# 9V_Converter.net
KiCad netlist of a schematic drawn in Altium Designer
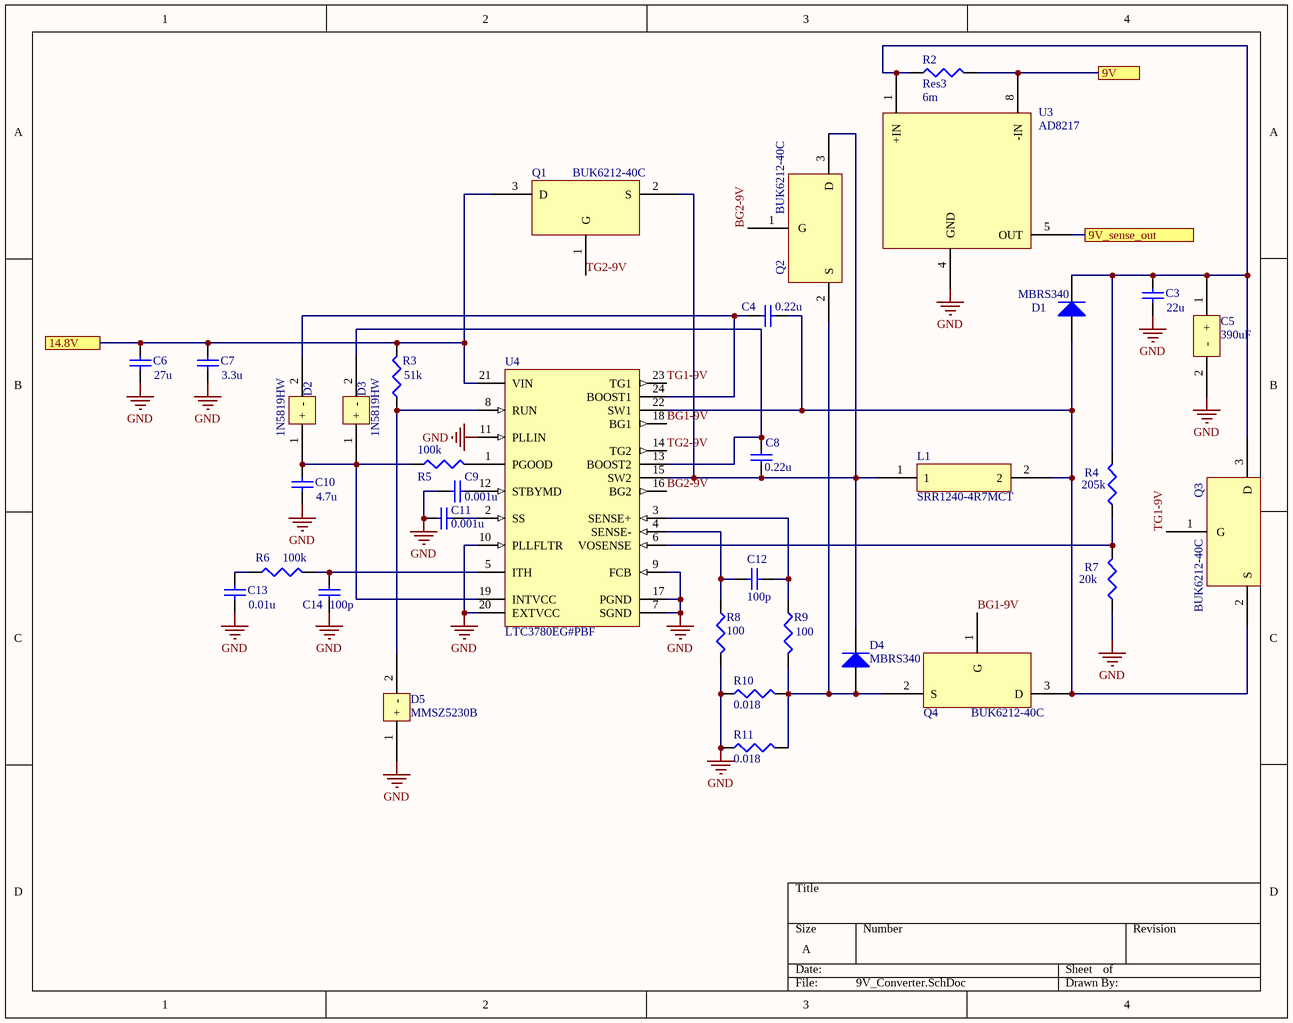
[diagram p0: 9V_Converter.SchDoc]

(export (version "E")
  (design (tool "Eeschema 10.0.6"))
  (components
    (comp (ref "C3")
      (value "22u")
      (footprint "C1206")
      (description "Capacitor (Semiconductor SIM Model)")
      (fields (field (name "Comment") "Cap Semi") (field (name "PUBLISHER") "Altium Limited"))
      (libsource (lib "Miscellaneous Devices") (part "Cap Semi"))
    )
    (comp (ref "C4")
      (value "0.22u")
      (footprint "C1206")
      (description "Capacitor (Semiconductor SIM Model)")
      (fields (field (name "Comment") "Cap Semi") (field (name "PUBLISHER") "Altium Limited"))
      (libsource (lib "Miscellaneous Devices") (part "Cap Semi"))
    )
    (comp (ref "C5")
      (value "390uF")
      (footprint "PCV1E391MCL2GS")
      (description "Aluminum Capacitor")
      (libsource (lib "Integrated_Library") (part "PCV1E391MCL2GS"))
    )
    (comp (ref "C6")
      (value "27u")
      (footprint "C1206")
      (description "Capacitor (Semiconductor SIM Model)")
      (fields (field (name "Comment") "Cap Semi") (field (name "PUBLISHER") "Altium Limited"))
      (libsource (lib "Miscellaneous Devices") (part "Cap Semi"))
    )
    (comp (ref "C7")
      (value "3.3u")
      (footprint "C1206")
      (description "Capacitor (Semiconductor SIM Model)")
      (fields (field (name "Comment") "Cap Semi") (field (name "PUBLISHER") "Altium Limited"))
      (libsource (lib "Miscellaneous Devices") (part "Cap Semi"))
    )
    (comp (ref "C8")
      (value "0.22u")
      (footprint "C1206")
      (description "Capacitor (Semiconductor SIM Model)")
      (fields (field (name "Comment") "Cap Semi") (field (name "PUBLISHER") "Altium Limited"))
      (libsource (lib "Miscellaneous Devices") (part "Cap Semi"))
    )
    (comp (ref "C9")
      (value "0.001u")
      (footprint "C1206")
      (description "Capacitor (Semiconductor SIM Model)")
      (fields (field (name "Comment") "Cap Semi") (field (name "PUBLISHER") "Altium Limited"))
      (libsource (lib "Miscellaneous Devices") (part "Cap Semi"))
    )
    (comp (ref "C10")
      (value "4.7u")
      (footprint "C1206")
      (description "Capacitor (Semiconductor SIM Model)")
      (fields (field (name "Comment") "Cap Semi") (field (name "PUBLISHER") "Altium Limited"))
      (libsource (lib "Miscellaneous Devices") (part "Cap Semi"))
    )
    (comp (ref "C11")
      (value "0.001u")
      (footprint "C1206")
      (description "Capacitor (Semiconductor SIM Model)")
      (fields (field (name "Comment") "Cap Semi") (field (name "PUBLISHER") "Altium Limited"))
      (libsource (lib "Miscellaneous Devices") (part "Cap Semi"))
    )
    (comp (ref "C12")
      (value "100p")
      (footprint "C1206")
      (description "Capacitor (Semiconductor SIM Model)")
      (fields (field (name "Comment") "Cap Semi") (field (name "PUBLISHER") "Altium Limited"))
      (libsource (lib "Miscellaneous Devices") (part "Cap Semi"))
    )
    (comp (ref "C13")
      (value "0.01u")
      (footprint "C1206")
      (description "Capacitor (Semiconductor SIM Model)")
      (fields (field (name "Comment") "Cap Semi") (field (name "PUBLISHER") "Altium Limited"))
      (libsource (lib "Miscellaneous Devices") (part "Cap Semi"))
    )
    (comp (ref "C14")
      (value "100p")
      (footprint "C1206")
      (description "Capacitor (Semiconductor SIM Model)")
      (fields (field (name "Comment") "Cap Semi") (field (name "PUBLISHER") "Altium Limited"))
      (libsource (lib "Miscellaneous Devices") (part "Cap Semi"))
    )
    (comp (ref "D1")
      (value "MBRS340")
      (footprint "SMC")
      (description "Default Diode")
      (fields (field (name "PUBLISHER") "Altium Limited"))
      (libsource (lib "Miscellaneous Devices") (part "Diode"))
    )
    (comp (ref "D2")
      (value "1N5819HW")
      (footprint "1N5819HW")
      (description "1A Schottky Barrier Rectifier")
      (libsource (lib "Integrated_Library") (part "1N5819HW"))
    )
    (comp (ref "D3")
      (value "1N5819HW")
      (footprint "1N5819HW")
      (description "1A Schottky Barrier Rectifier")
      (libsource (lib "Integrated_Library") (part "1N5819HW"))
    )
    (comp (ref "D4")
      (value "MBRS340")
      (footprint "SMC")
      (description "Default Diode")
      (fields (field (name "PUBLISHER") "Altium Limited"))
      (libsource (lib "Miscellaneous Devices") (part "Diode"))
    )
    (comp (ref "D5")
      (value "MMSZ5230B")
      (footprint "MMSZ5230B")
      (description "Zener Diode")
      (libsource (lib "Integrated_Library") (part "MMSZ5230B"))
    )
    (comp (ref "L1")
      (value "SRR1240-4R7MCT")
      (footprint "SRR1240-4R7M")
      (description "Inductor")
      (libsource (lib "Integrated_Library") (part "SRR1240-4R7MCT"))
    )
    (comp (ref "Q1")
      (value "BUK6212-40C")
      (footprint "BUK6212-40C")
      (description "N-Channel TrenchMOS Intermediate Level FET")
      (libsource (lib "Integrated_Library") (part "BUK6212-40C"))
    )
    (comp (ref "Q2")
      (value "BUK6212-40C")
      (footprint "BUK6212-40C")
      (description "N-Channel TrenchMOS Intermediate Level FET")
      (libsource (lib "") (part "BUK6212-40C_1"))
    )
    (comp (ref "Q3")
      (value "BUK6212-40C")
      (footprint "BUK6212-40C")
      (description "N-Channel TrenchMOS Intermediate Level FET")
      (libsource (lib "") (part "BUK6212-40C_1"))
    )
    (comp (ref "Q4")
      (value "BUK6212-40C")
      (footprint "BUK6212-40C")
      (description "N-Channel TrenchMOS Intermediate Level FET")
      (libsource (lib "") (part "BUK6212-40C_2"))
    )
    (comp (ref "R2")
      (value "Res3")
      (footprint "14-1210")
      (description "Resistor")
      (fields (field (name "ALTIUM_VALUE") "6m") (field (name "PUBLISHER") "Altium Limited"))
      (libsource (lib "Miscellaneous Devices") (part "Res3"))
    )
    (comp (ref "R3")
      (value "51k")
      (footprint "J1-0603")
      (description "Resistor")
      (fields (field (name "Comment") "Res3") (field (name "PUBLISHER") "Altium Limited"))
      (libsource (lib "Miscellaneous Devices") (part "Res3"))
    )
    (comp (ref "R4")
      (value "205k")
      (footprint "J1-0603")
      (description "Resistor")
      (fields (field (name "Comment") "Res3") (field (name "PUBLISHER") "Altium Limited"))
      (libsource (lib "Miscellaneous Devices") (part "Res3"))
    )
    (comp (ref "R5")
      (value "100k")
      (footprint "J1-0603")
      (description "Resistor")
      (fields (field (name "Comment") "Res3") (field (name "PUBLISHER") "Altium Limited"))
      (libsource (lib "Miscellaneous Devices") (part "Res3"))
    )
    (comp (ref "R6")
      (value "100k")
      (footprint "J1-0603")
      (description "Resistor")
      (fields (field (name "Comment") "Res3") (field (name "PUBLISHER") "Altium Limited"))
      (libsource (lib "Miscellaneous Devices") (part "Res3"))
    )
    (comp (ref "R7")
      (value "20k")
      (footprint "J1-0603")
      (description "Resistor")
      (fields (field (name "Comment") "Res3") (field (name "PUBLISHER") "Altium Limited"))
      (libsource (lib "Miscellaneous Devices") (part "Res3"))
    )
    (comp (ref "R8")
      (value "100")
      (footprint "J1-0603")
      (description "Resistor")
      (fields (field (name "Comment") "Res3") (field (name "PUBLISHER") "Altium Limited"))
      (libsource (lib "Miscellaneous Devices") (part "Res3"))
    )
    (comp (ref "R9")
      (value "100")
      (footprint "J1-0603")
      (description "Resistor")
      (fields (field (name "Comment") "Res3") (field (name "PUBLISHER") "Altium Limited"))
      (libsource (lib "Miscellaneous Devices") (part "Res3"))
    )
    (comp (ref "R10")
      (value "0.018")
      (footprint "14-1210")
      (description "Resistor")
      (fields (field (name "Comment") "Res3") (field (name "PUBLISHER") "Altium Limited"))
      (libsource (lib "Miscellaneous Devices") (part "Res3"))
    )
    (comp (ref "R11")
      (value "0.018")
      (footprint "14-1210")
      (description "Resistor")
      (fields (field (name "Comment") "Res3") (field (name "PUBLISHER") "Altium Limited"))
      (libsource (lib "Miscellaneous Devices") (part "Res3"))
    )
    (comp (ref "U3")
      (value "AD8217")
      (footprint "AD8217")
      (description "Current Shunt Moniter")
      (libsource (lib "Integrated_Library") (part "AD8217"))
    )
    (comp (ref "U4")
      (value "LTC3780EG#PBF")
      (footprint "LTC3780 24-Leaqd Plastic SSOP")
      (fields (field (name "MANUFACTURER") "Linear Technology"))
      (libsource (lib "Integrated_Library") (part "LTC3780EG#PBF"))
    )
  )
  (nets
    (net (code "1") (name "/9V") (class "Default")
      (node (ref "R2") (pin "2") (pinfunction "2_2") (pintype "passive"))
      (node (ref "U3") (pin "8") (pinfunction "-IN_8") (pintype "passive"))
    )
    (net (code "2") (name "/9V_sense_out") (class "Default")
      (node (ref "U3") (pin "5") (pinfunction "OUT_5") (pintype "passive"))
    )
    (net (code "3") (name "/14.8V") (class "Default")
      (node (ref "C6") (pin "2") (pinfunction "2_2") (pintype "passive"))
      (node (ref "C7") (pin "2") (pinfunction "2_2") (pintype "passive"))
      (node (ref "Q1") (pin "3") (pinfunction "D_3") (pintype "passive"))
      (node (ref "R3") (pin "2") (pinfunction "2_2") (pintype "passive"))
      (node (ref "U4") (pin "21") (pinfunction "VIN_21") (pintype "power_in"))
    )
    (net (code "4") (name "/BG1-9V") (class "Default")
      (node (ref "Q4") (pin "1") (pinfunction "G_1") (pintype "passive"))
      (node (ref "U4") (pin "18") (pinfunction "BG1_18") (pintype "output"))
    )
    (net (code "5") (name "/BG2-9V") (class "Default")
      (node (ref "Q2") (pin "1") (pinfunction "G_1") (pintype "passive"))
      (node (ref "U4") (pin "16") (pinfunction "BG2_16") (pintype "output"))
    )
    (net (code "6") (name "/TG1-9V") (class "Default")
      (node (ref "Q3") (pin "1") (pinfunction "G_1") (pintype "passive"))
      (node (ref "U4") (pin "23") (pinfunction "TG1_23") (pintype "output"))
    )
    (net (code "7") (name "/TG2-9V") (class "Default")
      (node (ref "Q1") (pin "1") (pinfunction "G_1") (pintype "passive"))
      (node (ref "U4") (pin "14") (pinfunction "TG2_14") (pintype "output"))
    )
    (net (code "8") (name "GND") (class "Default")
      (node (ref "C10") (pin "1") (pinfunction "1_1") (pintype "passive"))
      (node (ref "C11") (pin "1") (pinfunction "1_1") (pintype "passive"))
      (node (ref "C13") (pin "1") (pinfunction "1_1") (pintype "passive"))
      (node (ref "C14") (pin "1") (pinfunction "1_1") (pintype "passive"))
      (node (ref "C3") (pin "1") (pinfunction "1_1") (pintype "passive"))
      (node (ref "C5") (pin "2") (pinfunction "-_2") (pintype "passive"))
      (node (ref "C6") (pin "1") (pinfunction "1_1") (pintype "passive"))
      (node (ref "C7") (pin "1") (pinfunction "1_1") (pintype "passive"))
      (node (ref "C9") (pin "1") (pinfunction "1_1") (pintype "passive"))
      (node (ref "D5") (pin "1") (pinfunction "+_1") (pintype "passive"))
      (node (ref "R10") (pin "1") (pinfunction "1_1") (pintype "passive"))
      (node (ref "R11") (pin "1") (pinfunction "1_1") (pintype "passive"))
      (node (ref "R7") (pin "1") (pinfunction "1_1") (pintype "passive"))
      (node (ref "R8") (pin "2") (pinfunction "2_2") (pintype "passive"))
      (node (ref "U3") (pin "4") (pinfunction "GND_4") (pintype "passive"))
      (node (ref "U4") (pin "10") (pinfunction "PLLFLTR_10") (pintype "input"))
      (node (ref "U4") (pin "11") (pinfunction "PLLIN_11") (pintype "input"))
      (node (ref "U4") (pin "17") (pinfunction "PGND_17") (pintype "power_in"))
      (node (ref "U4") (pin "20") (pinfunction "EXTVCC_20") (pintype "power_in"))
      (node (ref "U4") (pin "7") (pinfunction "SGND_7") (pintype "power_in"))
      (node (ref "U4") (pin "9") (pinfunction "FCB_9") (pintype "input"))
    )
    (net (code "9") (name "Net-(C5-+)") (class "Default")
      (node (ref "C3") (pin "2") (pinfunction "2_2") (pintype "passive"))
      (node (ref "C5") (pin "1") (pinfunction "+_1") (pintype "passive"))
      (node (ref "D1") (pin "2") (pinfunction "K_2") (pintype "passive"))
      (node (ref "Q3") (pin "3") (pinfunction "D_3") (pintype "passive"))
      (node (ref "R2") (pin "1") (pinfunction "1_1") (pintype "passive"))
      (node (ref "R4") (pin "2") (pinfunction "2_2") (pintype "passive"))
      (node (ref "U3") (pin "1") (pinfunction "+IN_1") (pintype "passive"))
    )
    (net (code "10") (name "Net-(C13-Pad2)") (class "Default")
      (node (ref "C13") (pin "2") (pinfunction "2_2") (pintype "passive"))
      (node (ref "R6") (pin "1") (pinfunction "1_1") (pintype "passive"))
    )
    (net (code "11") (name "Net-(D1-A)") (class "Default")
      (node (ref "C4") (pin "1") (pinfunction "1_1") (pintype "passive"))
      (node (ref "D1") (pin "1") (pinfunction "A_1") (pintype "passive"))
      (node (ref "L1") (pin "2") (pinfunction "2_2") (pintype "passive"))
      (node (ref "Q3") (pin "2") (pinfunction "S_2") (pintype "passive"))
      (node (ref "Q4") (pin "3") (pinfunction "D_3") (pintype "passive"))
      (node (ref "U4") (pin "22") (pinfunction "SW1_22") (pintype "passive"))
    )
    (net (code "12") (name "Net-(D2-+)") (class "Default")
      (node (ref "C10") (pin "2") (pinfunction "2_2") (pintype "passive"))
      (node (ref "D2") (pin "1") (pinfunction "+_1") (pintype "passive"))
      (node (ref "D3") (pin "1") (pinfunction "+_1") (pintype "passive"))
      (node (ref "R5") (pin "1") (pinfunction "1_1") (pintype "passive"))
      (node (ref "U4") (pin "19") (pinfunction "INTVCC_19") (pintype "power_in"))
    )
    (net (code "13") (name "Net-(D2--)") (class "Default")
      (node (ref "C4") (pin "2") (pinfunction "2_2") (pintype "passive"))
      (node (ref "D2") (pin "2") (pinfunction "-_2") (pintype "passive"))
      (node (ref "U4") (pin "24") (pinfunction "BOOST1_24") (pintype "passive"))
    )
    (net (code "14") (name "Net-(D3--)") (class "Default")
      (node (ref "C8") (pin "2") (pinfunction "2_2") (pintype "passive"))
      (node (ref "D3") (pin "2") (pinfunction "-_2") (pintype "passive"))
      (node (ref "U4") (pin "13") (pinfunction "BOOST2_13") (pintype "passive"))
    )
    (net (code "15") (name "Net-(D4-A)") (class "Default")
      (node (ref "D4") (pin "1") (pinfunction "A_1") (pintype "passive"))
      (node (ref "Q2") (pin "2") (pinfunction "S_2") (pintype "passive"))
      (node (ref "Q4") (pin "2") (pinfunction "S_2") (pintype "passive"))
      (node (ref "R10") (pin "2") (pinfunction "2_2") (pintype "passive"))
      (node (ref "R11") (pin "2") (pinfunction "2_2") (pintype "passive"))
      (node (ref "R9") (pin "2") (pinfunction "2_2") (pintype "passive"))
    )
    (net (code "16") (name "Net-(D4-K)") (class "Default")
      (node (ref "C8") (pin "1") (pinfunction "1_1") (pintype "passive"))
      (node (ref "D4") (pin "2") (pinfunction "K_2") (pintype "passive"))
      (node (ref "L1") (pin "1") (pinfunction "1_1") (pintype "passive"))
      (node (ref "Q1") (pin "2") (pinfunction "S_2") (pintype "passive"))
      (node (ref "Q2") (pin "3") (pinfunction "D_3") (pintype "passive"))
      (node (ref "U4") (pin "15") (pinfunction "SW2_15") (pintype "passive"))
    )
    (net (code "17") (name "Net-(D5--)") (class "Default")
      (node (ref "D5") (pin "2") (pinfunction "-_2") (pintype "passive"))
      (node (ref "R3") (pin "1") (pinfunction "1_1") (pintype "passive"))
      (node (ref "U4") (pin "8") (pinfunction "RUN_8") (pintype "input"))
    )
    (net (code "18") (name "Net-(U4-ITH)") (class "Default")
      (node (ref "C14") (pin "2") (pinfunction "2_2") (pintype "passive"))
      (node (ref "R6") (pin "2") (pinfunction "2_2") (pintype "passive"))
      (node (ref "U4") (pin "5") (pinfunction "ITH_5") (pintype "passive"))
    )
    (net (code "19") (name "Net-(U4-PGOOD)") (class "Default")
      (node (ref "R5") (pin "2") (pinfunction "2_2") (pintype "passive"))
      (node (ref "U4") (pin "1") (pinfunction "PGOOD_1") (pintype "open_collector"))
    )
    (net (code "20") (name "Net-(U4-SENSE+)") (class "Default")
      (node (ref "C12") (pin "2") (pinfunction "2_2") (pintype "passive"))
      (node (ref "R9") (pin "1") (pinfunction "1_1") (pintype "passive"))
      (node (ref "U4") (pin "3") (pinfunction "SENSE+_3") (pintype "input"))
    )
    (net (code "21") (name "Net-(U4-SENSE-)") (class "Default")
      (node (ref "C12") (pin "1") (pinfunction "1_1") (pintype "passive"))
      (node (ref "R8") (pin "1") (pinfunction "1_1") (pintype "passive"))
      (node (ref "U4") (pin "4") (pinfunction "SENSE-_4") (pintype "input"))
    )
    (net (code "22") (name "Net-(U4-SS)") (class "Default")
      (node (ref "C11") (pin "2") (pinfunction "2_2") (pintype "passive"))
      (node (ref "U4") (pin "2") (pinfunction "SS_2") (pintype "input"))
    )
    (net (code "23") (name "Net-(U4-STBYMD)") (class "Default")
      (node (ref "C9") (pin "2") (pinfunction "2_2") (pintype "passive"))
      (node (ref "U4") (pin "12") (pinfunction "STBYMD_12") (pintype "input"))
    )
    (net (code "24") (name "Net-(U4-VOSENSE)") (class "Default")
      (node (ref "R4") (pin "1") (pinfunction "1_1") (pintype "passive"))
      (node (ref "R7") (pin "2") (pinfunction "2_2") (pintype "passive"))
      (node (ref "U4") (pin "6") (pinfunction "VOSENSE_6") (pintype "input"))
    )
  )
)
